# P02-DC_JACK.net
KiCad netlist of a schematic drawn in Altium Designer
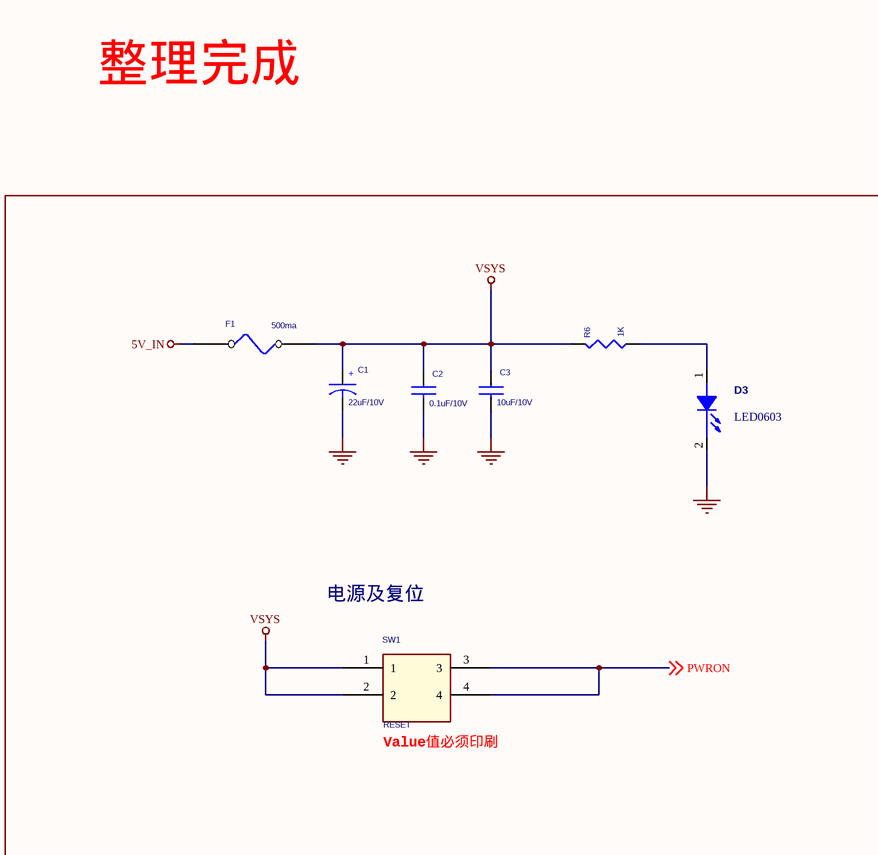
[diagram p0: P02-DC_JACK.SchDoc, top left]
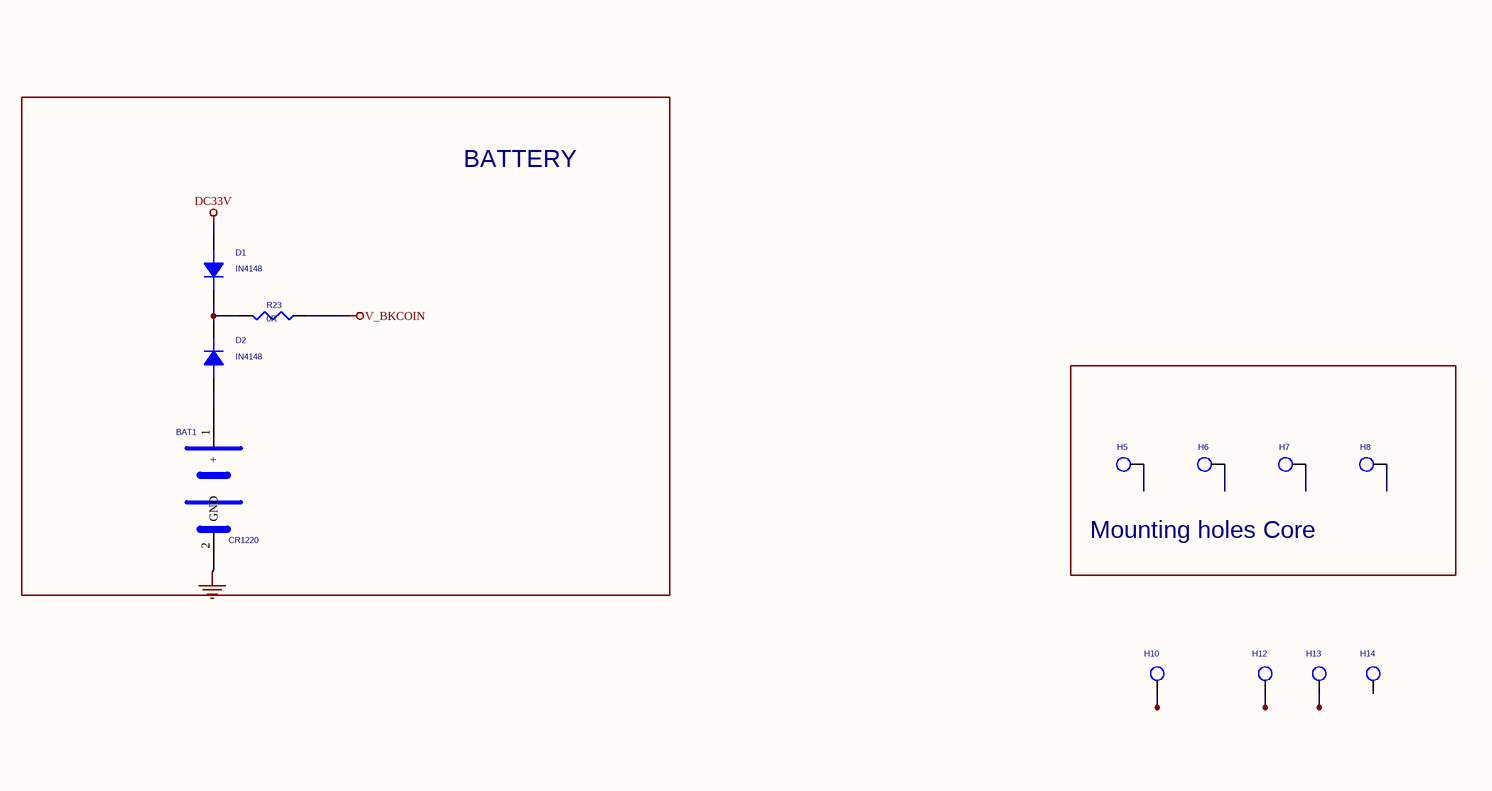
[diagram p1: P02-DC_JACK.SchDoc, top right]
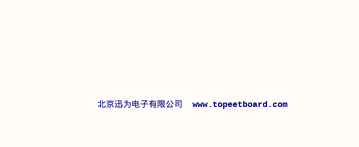
[diagram p2: P02-DC_JACK.SchDoc, bottom right]

(export (version "E")
  (design (tool "Eeschema 10.0.6"))
  (components
    (comp (ref "BAT1") (value "CR1220") (footprint "BAT1") (libsource (lib "*") (part "BATTERY_0")))
    (comp (ref "C1") (value "22uF/10V") (footprint "C1206-S") (libsource (lib "*") (part "CT2012_0")))
    (comp (ref "C2") (value "0.1uF/10V") (footprint "C0603-S") (libsource (lib "*") (part "C1608_Dup1")))
    (comp (ref "C3") (value "10uF/10V") (footprint "C0603-S") (libsource (lib "*") (part "C1608_Dup1")))
    (comp (ref "D1") (value "IN4148") (libsource (lib "*") (part "DIODE")))
    (comp (ref "D2") (value "IN4148") (libsource (lib "*") (part "DIODE")))
    (comp (ref "D3") (value "LED0603") (footprint "LED0603") (libsource (lib "*") (part "LED-RED_SMD_1")))
    (comp (ref "F1") (value "500ma") (libsource (lib "*") (part "FUSE")))
    (comp (ref "H5") (value "TP_P0_0.8_D0") (footprint "HOLE2_7") (libsource (lib "*") (part "TP_P0_0.8_D0")))
    (comp (ref "H6") (value "TP_P0_0.8_D0") (libsource (lib "*") (part "TP_P0_0.8_D0")))
    (comp (ref "H7") (value "TP_P0_0.8_D0") (libsource (lib "*") (part "TP_P0_0.8_D0")))
    (comp (ref "H8") (value "TP_P0_0.8_D0") (libsource (lib "*") (part "TP_P0_0.8_D0")))
    (comp (ref "H10")
      (value "TP_P0_0.8_D0")
      (footprint "HOLE2_7")
      (libsource (lib "*") (part "TP_P0_0.8_D0"))
    )
    (comp (ref "H12")
      (value "TP_P0_0.8_D0")
      (footprint "HOLE2_7")
      (libsource (lib "*") (part "TP_P0_0.8_D0"))
    )
    (comp (ref "H13")
      (value "TP_P0_0.8_D0")
      (footprint "HOLE2_7")
      (libsource (lib "*") (part "TP_P0_0.8_D0"))
    )
    (comp (ref "H14")
      (value "TP_P0_0.8_D0")
      (footprint "HOLE2_7")
      (libsource (lib "*") (part "TP_P0_0.8_D0"))
    )
    (comp (ref "R6") (value "1K") (footprint "R0603-S") (libsource (lib "*") (part "R1005_0_Dup1")))
    (comp (ref "R23") (value "0R") (libsource (lib "*") (part "R")))
    (comp (ref "SW1") (value "RESET") (footprint "SW4-SMD") (libsource (lib "*") (part "SW-4")))
  )
  (nets
    (net (code "1") (name "5V_IN") (class "Default")
      (node (ref "F1") (pin "1") (pinfunction "1_1") (pintype "passive"))
    )
    (net (code "2") (name "DC33V") (class "Default")
      (node (ref "D1") (pin "1") (pinfunction "A_1") (pintype "passive"))
    )
    (net (code "3") (name "GND") (class "Default")
      (node (ref "BAT1") (pin "2") (pinfunction "GND_2") (pintype "passive"))
      (node (ref "C1") (pin "2") (pinfunction "2_2") (pintype "passive"))
      (node (ref "C2") (pin "2") (pinfunction "2_2") (pintype "passive"))
      (node (ref "C3") (pin "2") (pinfunction "2_2") (pintype "passive"))
      (node (ref "D3") (pin "2") (pinfunction "CATHODE_2") (pintype "passive"))
    )
    (net (code "4") (name "Net-(BAT1-+)") (class "Default")
      (node (ref "BAT1") (pin "1") (pinfunction "+_1") (pintype "passive"))
      (node (ref "D2") (pin "1") (pinfunction "A_1") (pintype "passive"))
    )
    (net (code "5") (name "Net-(D1-K)") (class "Default")
      (node (ref "D1") (pin "2") (pinfunction "K_2") (pintype "passive"))
      (node (ref "D2") (pin "2") (pinfunction "K_2") (pintype "passive"))
      (node (ref "R23") (pin "2") (pinfunction "2_2") (pintype "passive"))
    )
    (net (code "6") (name "Net-(D3-ANODE)") (class "Default")
      (node (ref "D3") (pin "1") (pinfunction "ANODE_1") (pintype "passive"))
      (node (ref "R6") (pin "1") (pinfunction "1_1") (pintype "passive"))
    )
    (net (code "7") (name "PWRON") (class "Default")
      (node (ref "SW1") (pin "3") (pinfunction "3_3") (pintype "passive"))
      (node (ref "SW1") (pin "4") (pinfunction "4_4") (pintype "passive"))
    )
    (net (code "8") (name "VSYS") (class "Default")
      (node (ref "C1") (pin "1") (pinfunction "1_1") (pintype "passive"))
      (node (ref "C2") (pin "1") (pinfunction "1_1") (pintype "passive"))
      (node (ref "C3") (pin "1") (pinfunction "1_1") (pintype "passive"))
      (node (ref "F1") (pin "2") (pinfunction "2_2") (pintype "passive"))
      (node (ref "R6") (pin "2") (pinfunction "2_2") (pintype "passive"))
      (node (ref "SW1") (pin "1") (pinfunction "1_1") (pintype "passive"))
      (node (ref "SW1") (pin "2") (pinfunction "2_2") (pintype "passive"))
    )
    (net (code "9") (name "V_BKCOIN") (class "Default")
      (node (ref "R23") (pin "1") (pinfunction "1_1") (pintype "passive"))
    )
    (net (code "10") (name "unconnected-(H5-Pad1)") (class "Default")
      (node (ref "H5") (pin "1") (pinfunction "1_1") (pintype "passive"))
    )
    (net (code "11") (name "unconnected-(H6-Pad1)") (class "Default")
      (node (ref "H6") (pin "1") (pinfunction "1_1") (pintype "passive"))
    )
    (net (code "12") (name "unconnected-(H7-Pad1)") (class "Default")
      (node (ref "H7") (pin "1") (pinfunction "1_1") (pintype "passive"))
    )
    (net (code "13") (name "unconnected-(H8-Pad1)") (class "Default")
      (node (ref "H8") (pin "1") (pinfunction "1_1") (pintype "passive"))
    )
    (net (code "14") (name "unconnected-(H10-Pad1)") (class "Default")
      (node (ref "H10") (pin "1") (pinfunction "1_1") (pintype "passive"))
    )
    (net (code "15") (name "unconnected-(H12-Pad1)") (class "Default")
      (node (ref "H12") (pin "1") (pinfunction "1_1") (pintype "passive"))
    )
    (net (code "16") (name "unconnected-(H13-Pad1)") (class "Default")
      (node (ref "H13") (pin "1") (pinfunction "1_1") (pintype "passive"))
    )
    (net (code "17") (name "unconnected-(H14-Pad1)") (class "Default")
      (node (ref "H14") (pin "1") (pinfunction "1_1") (pintype "passive"))
    )
  )
)
